# LOG_AMP.net
KiCad netlist of a schematic drawn in Altium Designer
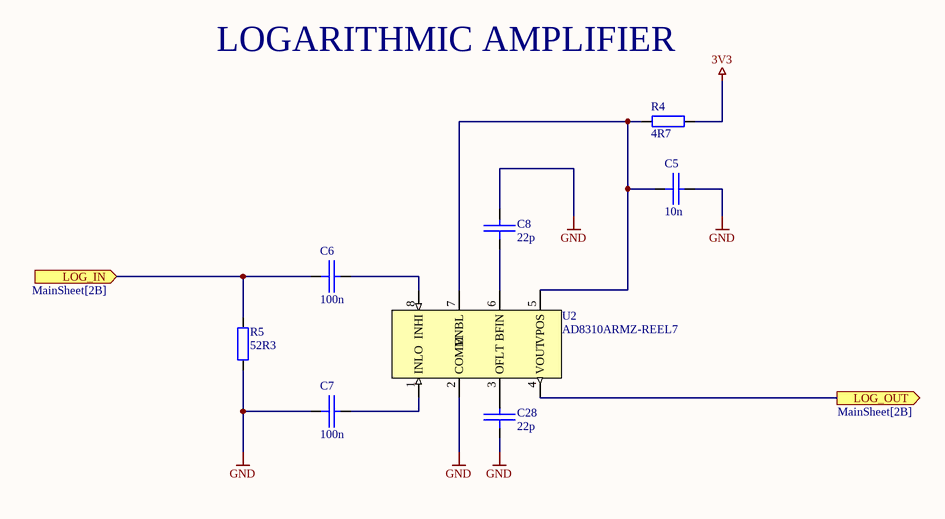
[diagram p0: LOG_AMP.SchDoc]

(export (version "E")
  (design (tool "Eeschema 10.0.6"))
  (components
    (comp (ref "C5")
      (value "10n")
      (footprint "0805")
      (description "Kondenzator, C0G, 10%, 50VDC")
      (fields
        (field (name "MANUFACTURER") "KEMET")
        (field (name "MANUFACTURER PART NUMBER") "C0805C103K5RECAUTO")
      )
      (libsource (lib "DZ1_Bruncic_Vito") (part "C0805C103K5RECAUTO"))
    )
    (comp (ref "C6")
      (value "100n")
      (footprint "0805")
      (description "Kondenzator, X7R, 10%, 50VDC")
      (fields
        (field (name "MANUFACTURER") "TDK")
        (field (name "MANUFACTURER PART NUMBER") "C2012X7R1H104K125AE")
      )
      (libsource (lib "DZ1_Bruncic_Vito") (part "MCJCU21GBB7104KTPA01"))
    )
    (comp (ref "C7")
      (value "100n")
      (footprint "0805")
      (description "Kondenzator, X7R, 10%, 50VDC")
      (fields
        (field (name "MANUFACTURER") "TDK")
        (field (name "MANUFACTURER PART NUMBER") "C2012X7R1H104K125AE")
      )
      (libsource (lib "DZ1_Bruncic_Vito") (part "MCJCU21GBB7104KTPA01"))
    )
    (comp (ref "C8")
      (value "22p")
      (footprint "0402")
      (description "Kondenzator, C0G, 1%, 50VDC")
      (libsource (lib "DZ1_Bruncic_Vito") (part "KAM05ACG1H220FH"))
    )
    (comp (ref "C28")
      (value "22p")
      (footprint "0402")
      (description "Kondenzator, C0G, 1%, 50VDC")
      (libsource (lib "DZ1_Bruncic_Vito") (part "KAM05ACG1H220FH"))
    )
    (comp (ref "R4")
      (value "4R7")
      (footprint "0805")
      (description "Otpornik, 1%, 125mW")
      (fields
        (field (name "MANUFACTURER") "Yageo")
        (field (name "MANUFACTURER PART NUMBER") "AC0805FR-074R7L")
      )
      (libsource (lib "DZ1_Bruncic_Vito") (part "AC0805FR-074R7L"))
    )
    (comp (ref "R5")
      (value "52R3")
      (footprint "0805")
      (description "Otpornik, 1%, 125mW")
      (fields
        (field (name "MANUFACTURER") "Yageo")
        (field (name "MANUFACTURER PART NUMBER") "RC0805FR-0752R3L")
      )
      (libsource (lib "DZ1_Bruncic_Vito") (part "RC0805FR-0752R3L"))
    )
    (comp (ref "U2")
      (value "AD8310ARMZ-REEL7")
      (footprint "MSOP")
      (description "Logaritamsko pojačalo")
      (fields (field (name "MANUFACTURER") "Analog Devices"))
      (libsource (lib "DZ1_Bruncic_Vito") (part "AD8310ARMZ-REEL7"))
    )
  )
  (nets
    (net (code "1") (name "/LOG_IN") (class "Default")
      (node (ref "C6") (pin "1") (pinfunction "1_1") (pintype "passive"))
      (node (ref "R5") (pin "2") (pinfunction "2_2") (pintype "passive"))
    )
    (net (code "2") (name "/LOG_OUT") (class "Default")
      (node (ref "U2") (pin "4") (pinfunction "VOUT_4") (pintype "output"))
    )
    (net (code "3") (name "3V3") (class "Default")
      (node (ref "R4") (pin "2") (pinfunction "2_2") (pintype "passive"))
    )
    (net (code "4") (name "GND") (class "Default")
      (node (ref "C28") (pin "1") (pinfunction "1_1") (pintype "passive"))
      (node (ref "C5") (pin "2") (pinfunction "2_2") (pintype "passive"))
      (node (ref "C7") (pin "1") (pinfunction "1_1") (pintype "passive"))
      (node (ref "C8") (pin "2") (pinfunction "2_2") (pintype "passive"))
      (node (ref "R5") (pin "1") (pinfunction "1_1") (pintype "passive"))
      (node (ref "U2") (pin "2") (pinfunction "COMM_2") (pintype "passive"))
    )
    (net (code "5") (name "Net-(U2-BFIN)") (class "Default")
      (node (ref "C8") (pin "1") (pinfunction "1_1") (pintype "passive"))
      (node (ref "U2") (pin "6") (pinfunction "BFIN_6") (pintype "passive"))
    )
    (net (code "6") (name "Net-(U2-ENBL)") (class "Default")
      (node (ref "C5") (pin "1") (pinfunction "1_1") (pintype "passive"))
      (node (ref "R4") (pin "1") (pinfunction "1_1") (pintype "passive"))
      (node (ref "U2") (pin "5") (pinfunction "VPOS_5") (pintype "power_in"))
      (node (ref "U2") (pin "7") (pinfunction "ENBL_7") (pintype "power_in"))
    )
    (net (code "7") (name "Net-(U2-INHI)") (class "Default")
      (node (ref "C6") (pin "2") (pinfunction "2_2") (pintype "passive"))
      (node (ref "U2") (pin "8") (pinfunction "INHI_8") (pintype "input"))
    )
    (net (code "8") (name "Net-(U2-INLO)") (class "Default")
      (node (ref "C7") (pin "2") (pinfunction "2_2") (pintype "passive"))
      (node (ref "U2") (pin "1") (pinfunction "INLO_1") (pintype "input"))
    )
    (net (code "9") (name "Net-(U2-OFLT)") (class "Default")
      (node (ref "C28") (pin "2") (pinfunction "2_2") (pintype "passive"))
      (node (ref "U2") (pin "3") (pinfunction "OFLT_3") (pintype "passive"))
    )
  )
)
